# ASD2111.net
KiCad netlist of a schematic drawn in EAGLE
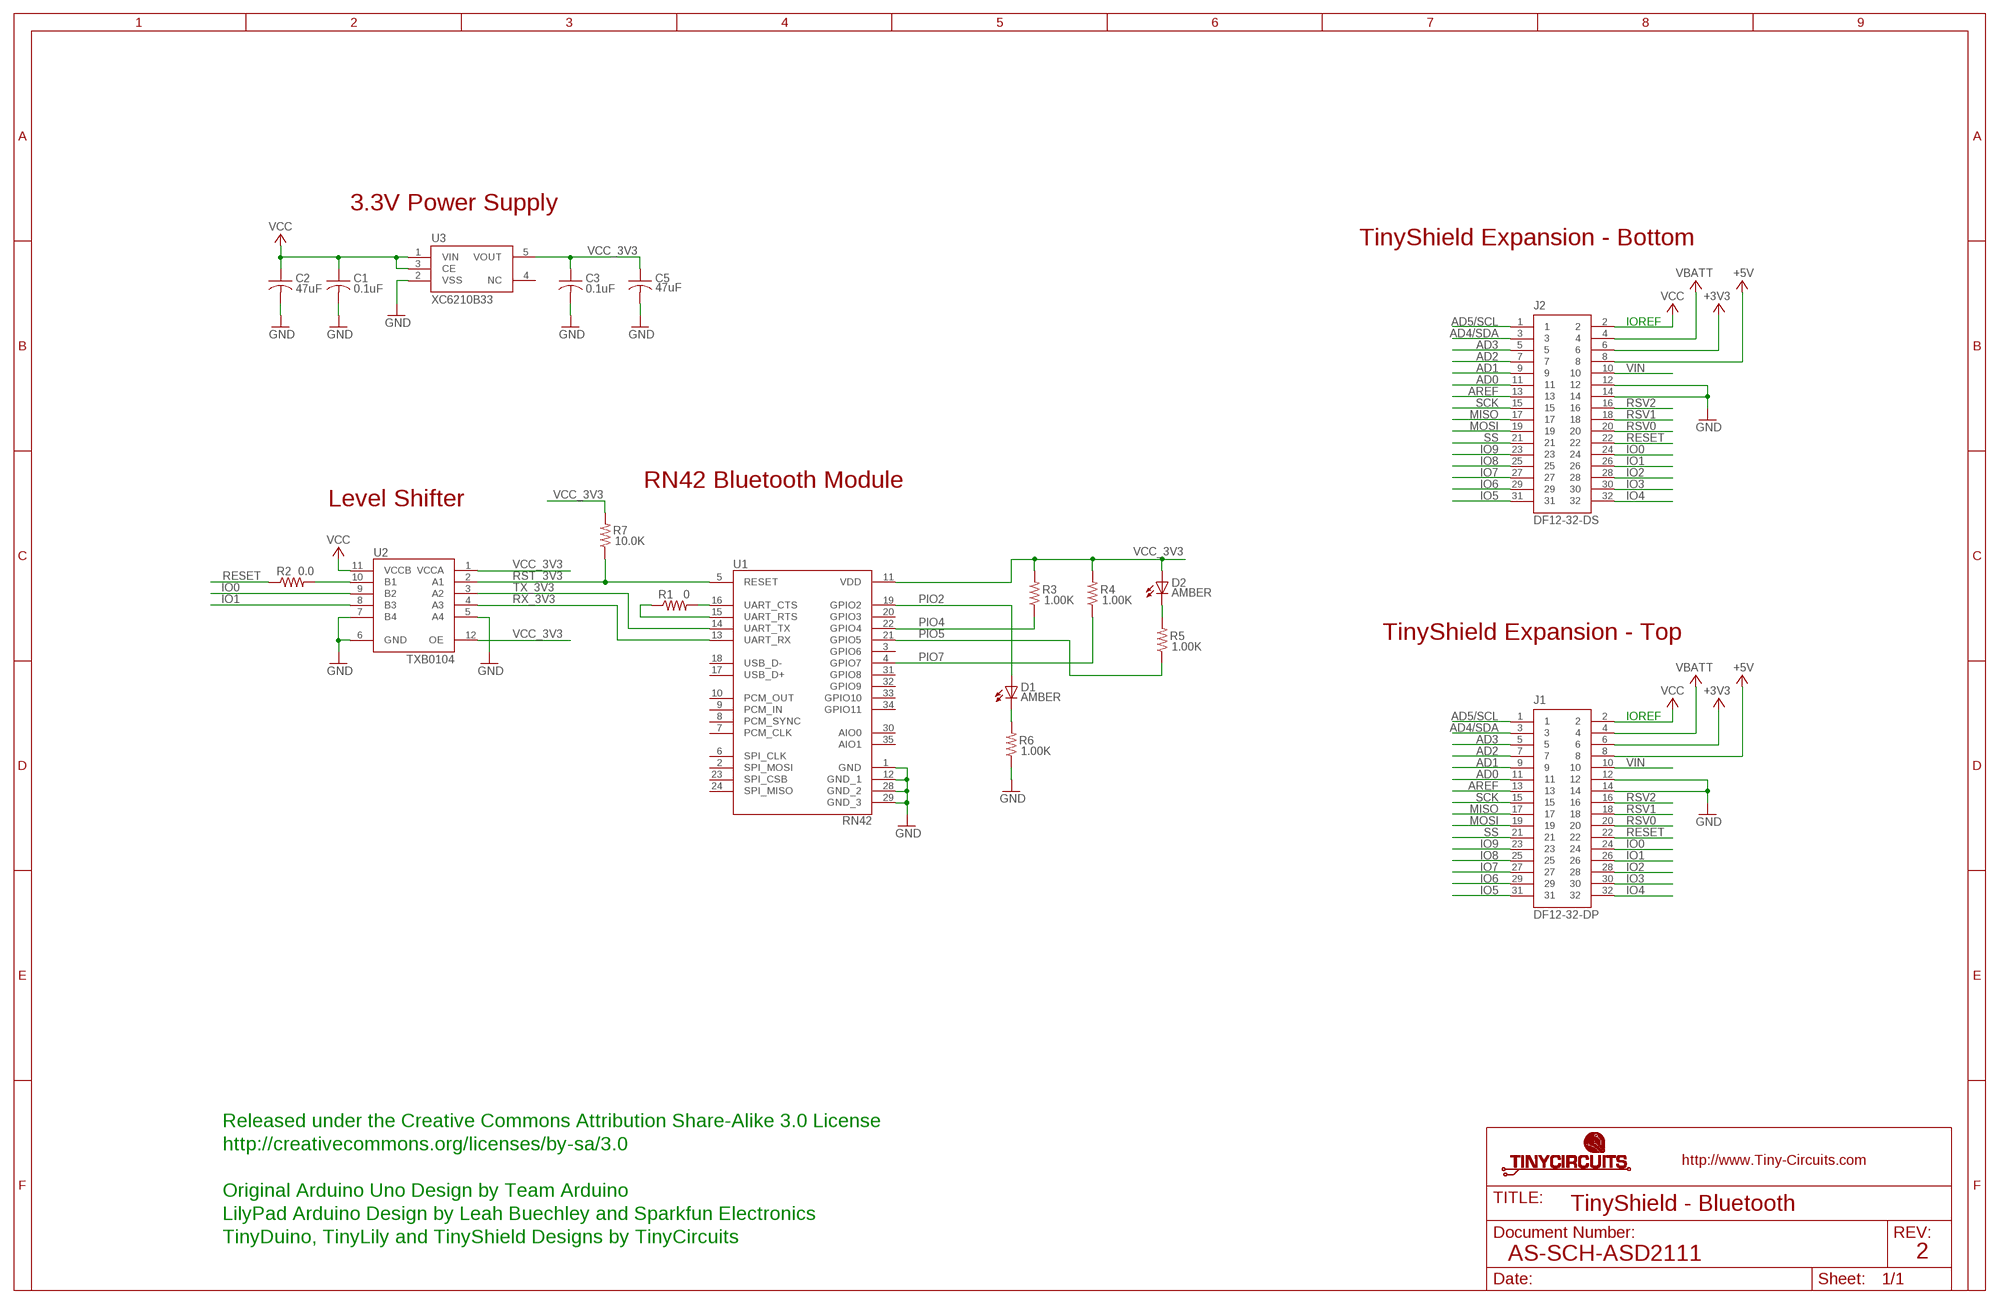
[diagram p0: schematic, sheet 1]

(export (version "E")
  (design (tool "Eeschema 10.0.6"))
  (components
    (comp (ref "C1")
      (value "0.1uF")
      (footprint "eagle-import:C0402")
      (fields (field (name "PARTNO") "AS-ITM-00008") (field (name "PARTNO_1") "AS-ITM-00008"))
      (libsource (lib "eagle-import") (part "AS-ITM-00008"))
    )
    (comp (ref "C2")
      (value "47uF")
      (footprint "eagle-import:C1206")
      (fields (field (name "PARTNUM") "AS-ITM-00049") (field (name "PARTNUM_1") "AS-ITM-00049"))
      (libsource (lib "eagle-import") (part "AS-ITM-00049"))
    )
    (comp (ref "C3")
      (value "0.1uF")
      (footprint "eagle-import:C0402")
      (fields (field (name "PARTNO") "AS-ITM-00008") (field (name "PARTNO_1") "AS-ITM-00008"))
      (libsource (lib "eagle-import") (part "AS-ITM-00008"))
    )
    (comp (ref "C5")
      (value "47uF")
      (footprint "eagle-import:C1206")
      (fields (field (name "PARTNUM") "AS-ITM-00049"))
      (libsource (lib "eagle-import") (part "AS-ITM-00049"))
    )
    (comp (ref "D1")
      (value "AMBER")
      (footprint "eagle-import:LNJ_LED")
      (fields (field (name "PARTNO") "AS-ITM-00026"))
      (libsource (lib "eagle-import") (part "AS-ITM-00026"))
    )
    (comp (ref "D2")
      (value "AMBER")
      (footprint "eagle-import:LNJ_LED")
      (fields (field (name "PARTNO") "AS-ITM-00026") (field (name "PARTNO_1") "AS-ITM-00026"))
      (libsource (lib "eagle-import") (part "AS-ITM-00026"))
    )
    (comp (ref "J1")
      (value "DF12-32-DP")
      (footprint "eagle-import:DF12-32-DP")
      (fields (field (name "PARTNO") "AS-ITM-00015") (field (name "PARTNO_1") "AS-ITM-00015"))
      (libsource (lib "eagle-import") (part "AS-ITM-00015"))
    )
    (comp (ref "J2")
      (value "DF12-32-DS")
      (footprint "eagle-import:DF12-32-DS")
      (fields (field (name "PARTNO") "AS-ITM-00012") (field (name "PARTNO_1") "AS-ITM-00012"))
      (libsource (lib "eagle-import") (part "AS-ITM-00012"))
    )
    (comp (ref "R1")
      (value "0")
      (footprint "eagle-import:0402_SHORT")
      (libsource (lib "eagle-import") (part "AS-ITM-000760402_SHORT"))
    )
    (comp (ref "R2")
      (value "0.0")
      (footprint "eagle-import:0402")
      (fields (field (name "PARTNO") "AS-ITM-00076"))
      (libsource (lib "eagle-import") (part "AS-ITM-00076"))
    )
    (comp (ref "R3")
      (value "1.00K")
      (footprint "eagle-import:0402")
      (fields (field (name "PARTNO") "AS-ITM-00003"))
      (libsource (lib "eagle-import") (part "AS-ITM-00003"))
    )
    (comp (ref "R4")
      (value "1.00K")
      (footprint "eagle-import:0402")
      (fields (field (name "PARTNO") "AS-ITM-00003") (field (name "PARTNO_1") "AS-ITM-00003"))
      (libsource (lib "eagle-import") (part "AS-ITM-00003"))
    )
    (comp (ref "R5")
      (value "1.00K")
      (footprint "eagle-import:0402")
      (fields (field (name "PARTNO") "AS-ITM-00003") (field (name "PARTNO_1") "AS-ITM-00003"))
      (libsource (lib "eagle-import") (part "AS-ITM-00003"))
    )
    (comp (ref "R6")
      (value "1.00K")
      (footprint "eagle-import:0402")
      (fields (field (name "PARTNO") "AS-ITM-00003") (field (name "PARTNO_1") "AS-ITM-00003"))
      (libsource (lib "eagle-import") (part "AS-ITM-00003"))
    )
    (comp (ref "R7")
      (value "10.0K")
      (footprint "eagle-import:0402")
      (fields (field (name "PARTNO") "AS-ITM-00032"))
      (libsource (lib "eagle-import") (part "AS-ITM-00032"))
    )
    (comp (ref "U1")
      (value "RN42")
      (footprint "eagle-import:RN42_BLUETOOTH_MODULE")
      (fields (field (name "PARTNO") "AS-ITM-00071"))
      (libsource (lib "eagle-import") (part "AS-ITM-00071"))
    )
    (comp (ref "U2")
      (value "TXB0104")
      (footprint "eagle-import:UQFN-12")
      (fields (field (name "PARTNO") "AS-ITM-00048"))
      (libsource (lib "eagle-import") (part "AS-ITM-00048"))
    )
    (comp (ref "U3")
      (value "XC6210B33")
      (footprint "eagle-import:SOT-25")
      (fields (field (name "PARTNO") "AS-ITM-00046"))
      (libsource (lib "eagle-import") (part "AS-ITM-00046"))
    )
  )
  (nets
    (net (code "1") (name "+3V3") (class "Default")
      (node (ref "J1") (pin "6") (pinfunction "6_6") (pintype "bidirectional"))
      (node (ref "J2") (pin "6") (pinfunction "6_6") (pintype "bidirectional"))
    )
    (net (code "2") (name "+5V") (class "Default")
      (node (ref "J1") (pin "8") (pinfunction "8_8") (pintype "bidirectional"))
      (node (ref "J2") (pin "8") (pinfunction "8_8") (pintype "bidirectional"))
    )
    (net (code "3") (name "/AD0") (class "Default")
      (node (ref "J1") (pin "11") (pinfunction "11_11") (pintype "bidirectional"))
      (node (ref "J2") (pin "11") (pinfunction "11_11") (pintype "bidirectional"))
    )
    (net (code "4") (name "/AD1") (class "Default")
      (node (ref "J1") (pin "9") (pinfunction "9_9") (pintype "bidirectional"))
      (node (ref "J2") (pin "9") (pinfunction "9_9") (pintype "bidirectional"))
    )
    (net (code "5") (name "/AD2") (class "Default")
      (node (ref "J1") (pin "7") (pinfunction "7_7") (pintype "bidirectional"))
      (node (ref "J2") (pin "7") (pinfunction "7_7") (pintype "bidirectional"))
    )
    (net (code "6") (name "/AD3") (class "Default")
      (node (ref "J1") (pin "5") (pinfunction "5_5") (pintype "bidirectional"))
      (node (ref "J2") (pin "5") (pinfunction "5_5") (pintype "bidirectional"))
    )
    (net (code "7") (name "/AD4{slash}SDA") (class "Default")
      (node (ref "J1") (pin "3") (pinfunction "3_3") (pintype "bidirectional"))
      (node (ref "J2") (pin "3") (pinfunction "3_3") (pintype "bidirectional"))
    )
    (net (code "8") (name "/AD5{slash}SCL") (class "Default")
      (node (ref "J1") (pin "1") (pinfunction "1_1") (pintype "bidirectional"))
      (node (ref "J2") (pin "1") (pinfunction "1_1") (pintype "bidirectional"))
    )
    (net (code "9") (name "/AREF") (class "Default")
      (node (ref "J1") (pin "13") (pinfunction "13_13") (pintype "bidirectional"))
      (node (ref "J2") (pin "13") (pinfunction "13_13") (pintype "bidirectional"))
    )
    (net (code "10") (name "/IO0") (class "Default")
      (node (ref "J1") (pin "24") (pinfunction "24_24") (pintype "bidirectional"))
      (node (ref "J2") (pin "24") (pinfunction "24_24") (pintype "bidirectional"))
      (node (ref "U2") (pin "9") (pinfunction "B2_9") (pintype "bidirectional"))
    )
    (net (code "11") (name "/IO1") (class "Default")
      (node (ref "J1") (pin "26") (pinfunction "26_26") (pintype "bidirectional"))
      (node (ref "J2") (pin "26") (pinfunction "26_26") (pintype "bidirectional"))
      (node (ref "U2") (pin "8") (pinfunction "B3_8") (pintype "bidirectional"))
    )
    (net (code "12") (name "/IO2") (class "Default")
      (node (ref "J1") (pin "28") (pinfunction "28_28") (pintype "bidirectional"))
      (node (ref "J2") (pin "28") (pinfunction "28_28") (pintype "bidirectional"))
    )
    (net (code "13") (name "/IO3") (class "Default")
      (node (ref "J1") (pin "30") (pinfunction "30_30") (pintype "bidirectional"))
      (node (ref "J2") (pin "30") (pinfunction "30_30") (pintype "bidirectional"))
    )
    (net (code "14") (name "/IO4") (class "Default")
      (node (ref "J1") (pin "32") (pinfunction "32_32") (pintype "bidirectional"))
      (node (ref "J2") (pin "32") (pinfunction "32_32") (pintype "bidirectional"))
    )
    (net (code "15") (name "/IO5") (class "Default")
      (node (ref "J1") (pin "31") (pinfunction "31_31") (pintype "bidirectional"))
      (node (ref "J2") (pin "31") (pinfunction "31_31") (pintype "bidirectional"))
    )
    (net (code "16") (name "/IO6") (class "Default")
      (node (ref "J1") (pin "29") (pinfunction "29_29") (pintype "bidirectional"))
      (node (ref "J2") (pin "29") (pinfunction "29_29") (pintype "bidirectional"))
    )
    (net (code "17") (name "/IO7") (class "Default")
      (node (ref "J1") (pin "27") (pinfunction "27_27") (pintype "bidirectional"))
      (node (ref "J2") (pin "27") (pinfunction "27_27") (pintype "bidirectional"))
    )
    (net (code "18") (name "/IO8") (class "Default")
      (node (ref "J1") (pin "25") (pinfunction "25_25") (pintype "bidirectional"))
      (node (ref "J2") (pin "25") (pinfunction "25_25") (pintype "bidirectional"))
    )
    (net (code "19") (name "/IO9") (class "Default")
      (node (ref "J1") (pin "23") (pinfunction "23_23") (pintype "bidirectional"))
      (node (ref "J2") (pin "23") (pinfunction "23_23") (pintype "bidirectional"))
    )
    (net (code "20") (name "/MISO") (class "Default")
      (node (ref "J1") (pin "17") (pinfunction "17_17") (pintype "bidirectional"))
      (node (ref "J2") (pin "17") (pinfunction "17_17") (pintype "bidirectional"))
    )
    (net (code "21") (name "/MOSI") (class "Default")
      (node (ref "J1") (pin "19") (pinfunction "19_19") (pintype "bidirectional"))
      (node (ref "J2") (pin "19") (pinfunction "19_19") (pintype "bidirectional"))
    )
    (net (code "22") (name "/PIO2") (class "Default")
      (node (ref "D1") (pin "A") (pinfunction "A_A") (pintype "passive"))
      (node (ref "U1") (pin "19") (pinfunction "GPIO2_19") (pintype "bidirectional"))
    )
    (net (code "23") (name "/PIO4") (class "Default")
      (node (ref "R3") (pin "1") (pinfunction "1_1") (pintype "passive"))
      (node (ref "U1") (pin "22") (pinfunction "GPIO4_22") (pintype "bidirectional"))
    )
    (net (code "24") (name "/PIO5") (class "Default")
      (node (ref "R5") (pin "1") (pinfunction "1_1") (pintype "passive"))
      (node (ref "U1") (pin "21") (pinfunction "GPIO5_21") (pintype "bidirectional"))
    )
    (net (code "25") (name "/PIO7") (class "Default")
      (node (ref "R4") (pin "1") (pinfunction "1_1") (pintype "passive"))
      (node (ref "U1") (pin "4") (pinfunction "GPIO7_4") (pintype "bidirectional"))
    )
    (net (code "26") (name "/RESET") (class "Default")
      (node (ref "J1") (pin "22") (pinfunction "22_22") (pintype "bidirectional"))
      (node (ref "J2") (pin "22") (pinfunction "22_22") (pintype "bidirectional"))
      (node (ref "R2") (pin "1") (pinfunction "1_1") (pintype "passive"))
    )
    (net (code "27") (name "/RST_3V3") (class "Default")
      (node (ref "R7") (pin "1") (pinfunction "1_1") (pintype "passive"))
      (node (ref "U1") (pin "5") (pinfunction "RESET_5") (pintype "bidirectional"))
      (node (ref "U2") (pin "2") (pinfunction "A1_2") (pintype "bidirectional"))
    )
    (net (code "28") (name "/RSV0") (class "Default")
      (node (ref "J1") (pin "20") (pinfunction "20_20") (pintype "bidirectional"))
      (node (ref "J2") (pin "20") (pinfunction "20_20") (pintype "bidirectional"))
    )
    (net (code "29") (name "/RSV1") (class "Default")
      (node (ref "J1") (pin "18") (pinfunction "18_18") (pintype "bidirectional"))
      (node (ref "J2") (pin "18") (pinfunction "18_18") (pintype "bidirectional"))
    )
    (net (code "30") (name "/RSV2") (class "Default")
      (node (ref "J1") (pin "16") (pinfunction "16_16") (pintype "bidirectional"))
      (node (ref "J2") (pin "16") (pinfunction "16_16") (pintype "bidirectional"))
    )
    (net (code "31") (name "/RX_3V3") (class "Default")
      (node (ref "U1") (pin "13") (pinfunction "UART_RX_13") (pintype "bidirectional"))
      (node (ref "U2") (pin "4") (pinfunction "A3_4") (pintype "bidirectional"))
    )
    (net (code "32") (name "/SCK") (class "Default")
      (node (ref "J1") (pin "15") (pinfunction "15_15") (pintype "bidirectional"))
      (node (ref "J2") (pin "15") (pinfunction "15_15") (pintype "bidirectional"))
    )
    (net (code "33") (name "/SS") (class "Default")
      (node (ref "J1") (pin "21") (pinfunction "21_21") (pintype "bidirectional"))
      (node (ref "J2") (pin "21") (pinfunction "21_21") (pintype "bidirectional"))
    )
    (net (code "34") (name "/TX_3V3") (class "Default")
      (node (ref "U1") (pin "14") (pinfunction "UART_TX_14") (pintype "bidirectional"))
      (node (ref "U2") (pin "3") (pinfunction "A2_3") (pintype "bidirectional"))
    )
    (net (code "35") (name "/VCC_3V3") (class "Default")
      (node (ref "C3") (pin "1") (pinfunction "1_1") (pintype "passive"))
      (node (ref "C5") (pin "1") (pinfunction "1_1") (pintype "passive"))
      (node (ref "D2") (pin "A") (pinfunction "A_A") (pintype "passive"))
      (node (ref "R3") (pin "2") (pinfunction "2_2") (pintype "passive"))
      (node (ref "R4") (pin "2") (pinfunction "2_2") (pintype "passive"))
      (node (ref "R7") (pin "2") (pinfunction "2_2") (pintype "passive"))
      (node (ref "U1") (pin "11") (pinfunction "VDD_11") (pintype "bidirectional"))
      (node (ref "U2") (pin "1") (pinfunction "VCCA_1") (pintype "bidirectional"))
      (node (ref "U2") (pin "12") (pinfunction "OE_12") (pintype "bidirectional"))
      (node (ref "U3") (pin "5") (pinfunction "VOUT_5") (pintype "bidirectional"))
    )
    (net (code "36") (name "/VIN") (class "Default")
      (node (ref "J1") (pin "10") (pinfunction "10_10") (pintype "bidirectional"))
      (node (ref "J2") (pin "10") (pinfunction "10_10") (pintype "bidirectional"))
    )
    (net (code "37") (name "GND") (class "Default")
      (node (ref "C1") (pin "2") (pinfunction "2_2") (pintype "passive"))
      (node (ref "C2") (pin "2") (pinfunction "2_2") (pintype "passive"))
      (node (ref "C3") (pin "2") (pinfunction "2_2") (pintype "passive"))
      (node (ref "C5") (pin "2") (pinfunction "2_2") (pintype "passive"))
      (node (ref "J1") (pin "12") (pinfunction "12_12") (pintype "bidirectional"))
      (node (ref "J1") (pin "14") (pinfunction "14_14") (pintype "bidirectional"))
      (node (ref "J2") (pin "12") (pinfunction "12_12") (pintype "bidirectional"))
      (node (ref "J2") (pin "14") (pinfunction "14_14") (pintype "bidirectional"))
      (node (ref "R6") (pin "1") (pinfunction "1_1") (pintype "passive"))
      (node (ref "U1") (pin "1") (pinfunction "GND_1") (pintype "bidirectional"))
      (node (ref "U1") (pin "12") (pinfunction "GND_1_12") (pintype "bidirectional"))
      (node (ref "U1") (pin "28") (pinfunction "GND_2_28") (pintype "bidirectional"))
      (node (ref "U1") (pin "29") (pinfunction "GND_3_29") (pintype "bidirectional"))
      (node (ref "U2") (pin "5") (pinfunction "A4_5") (pintype "bidirectional"))
      (node (ref "U2") (pin "6") (pinfunction "GND_6") (pintype "bidirectional"))
      (node (ref "U2") (pin "7") (pinfunction "B4_7") (pintype "bidirectional"))
      (node (ref "U3") (pin "2") (pinfunction "VSS_2") (pintype "power_in"))
    )
    (net (code "38") (name "Net-(D1-PadC)") (class "Default")
      (node (ref "D1") (pin "C") (pinfunction "C_C") (pintype "passive"))
      (node (ref "R6") (pin "2") (pinfunction "2_2") (pintype "passive"))
    )
    (net (code "39") (name "Net-(D2-PadC)") (class "Default")
      (node (ref "D2") (pin "C") (pinfunction "C_C") (pintype "passive"))
      (node (ref "R5") (pin "2") (pinfunction "2_2") (pintype "passive"))
    )
    (net (code "40") (name "Net-(U1-UART_CTS)") (class "Default")
      (node (ref "R1") (pin "2") (pinfunction "2_2") (pintype "passive"))
      (node (ref "U1") (pin "16") (pinfunction "UART_CTS_16") (pintype "bidirectional"))
    )
    (net (code "41") (name "Net-(U1-UART_RTS)") (class "Default")
      (node (ref "R1") (pin "1") (pinfunction "1_1") (pintype "passive"))
      (node (ref "U1") (pin "15") (pinfunction "UART_RTS_15") (pintype "bidirectional"))
    )
    (net (code "42") (name "Net-(U2-B1)") (class "Default")
      (node (ref "R2") (pin "2") (pinfunction "2_2") (pintype "passive"))
      (node (ref "U2") (pin "10") (pinfunction "B1_10") (pintype "bidirectional"))
    )
    (net (code "43") (name "VBATT") (class "Default")
      (node (ref "J1") (pin "4") (pinfunction "4_4") (pintype "bidirectional"))
      (node (ref "J2") (pin "4") (pinfunction "4_4") (pintype "bidirectional"))
    )
    (net (code "44") (name "VCC") (class "Default")
      (node (ref "C1") (pin "1") (pinfunction "1_1") (pintype "passive"))
      (node (ref "C2") (pin "1") (pinfunction "1_1") (pintype "passive"))
      (node (ref "J1") (pin "2") (pinfunction "2_2") (pintype "bidirectional"))
      (node (ref "J2") (pin "2") (pinfunction "2_2") (pintype "bidirectional"))
      (node (ref "U2") (pin "11") (pinfunction "VCCB_11") (pintype "bidirectional"))
      (node (ref "U3") (pin "1") (pinfunction "VIN_1") (pintype "bidirectional"))
      (node (ref "U3") (pin "3") (pinfunction "CE_3") (pintype "bidirectional"))
    )
    (net (code "45") (name "unconnected-(U1-AIO0-Pad30)") (class "Default")
      (node (ref "U1") (pin "30") (pinfunction "AIO0_30") (pintype "bidirectional"))
    )
    (net (code "46") (name "unconnected-(U1-AIO1-Pad35)") (class "Default")
      (node (ref "U1") (pin "35") (pinfunction "AIO1_35") (pintype "bidirectional"))
    )
    (net (code "47") (name "unconnected-(U1-GPIO3-Pad20)") (class "Default")
      (node (ref "U1") (pin "20") (pinfunction "GPIO3_20") (pintype "bidirectional"))
    )
    (net (code "48") (name "unconnected-(U1-GPIO6-Pad3)") (class "Default")
      (node (ref "U1") (pin "3") (pinfunction "GPIO6_3") (pintype "bidirectional"))
    )
    (net (code "49") (name "unconnected-(U1-GPIO8-Pad31)") (class "Default")
      (node (ref "U1") (pin "31") (pinfunction "GPIO8_31") (pintype "bidirectional"))
    )
    (net (code "50") (name "unconnected-(U1-GPIO9-Pad32)") (class "Default")
      (node (ref "U1") (pin "32") (pinfunction "GPIO9_32") (pintype "bidirectional"))
    )
    (net (code "51") (name "unconnected-(U1-GPIO10-Pad33)") (class "Default")
      (node (ref "U1") (pin "33") (pinfunction "GPIO10_33") (pintype "bidirectional"))
    )
    (net (code "52") (name "unconnected-(U1-GPIO11-Pad34)") (class "Default")
      (node (ref "U1") (pin "34") (pinfunction "GPIO11_34") (pintype "bidirectional"))
    )
    (net (code "53") (name "unconnected-(U1-PCM_CLK-Pad7)") (class "Default")
      (node (ref "U1") (pin "7") (pinfunction "PCM_CLK_7") (pintype "bidirectional"))
    )
    (net (code "54") (name "unconnected-(U1-PCM_IN-Pad9)") (class "Default")
      (node (ref "U1") (pin "9") (pinfunction "PCM_IN_9") (pintype "bidirectional"))
    )
    (net (code "55") (name "unconnected-(U1-PCM_OUT-Pad10)") (class "Default")
      (node (ref "U1") (pin "10") (pinfunction "PCM_OUT_10") (pintype "bidirectional"))
    )
    (net (code "56") (name "unconnected-(U1-PCM_SYNC-Pad8)") (class "Default")
      (node (ref "U1") (pin "8") (pinfunction "PCM_SYNC_8") (pintype "bidirectional"))
    )
    (net (code "57") (name "unconnected-(U1-SPI_CLK-Pad6)") (class "Default")
      (node (ref "U1") (pin "6") (pinfunction "SPI_CLK_6") (pintype "bidirectional"))
    )
    (net (code "58") (name "unconnected-(U1-SPI_CSB-Pad23)") (class "Default")
      (node (ref "U1") (pin "23") (pinfunction "SPI_CSB_23") (pintype "bidirectional"))
    )
    (net (code "59") (name "unconnected-(U1-SPI_MISO-Pad24)") (class "Default")
      (node (ref "U1") (pin "24") (pinfunction "SPI_MISO_24") (pintype "bidirectional"))
    )
    (net (code "60") (name "unconnected-(U1-SPI_MOSI-Pad2)") (class "Default")
      (node (ref "U1") (pin "2") (pinfunction "SPI_MOSI_2") (pintype "bidirectional"))
    )
    (net (code "61") (name "unconnected-(U1-USB_D+-Pad17)") (class "Default")
      (node (ref "U1") (pin "17") (pinfunction "USB_D+_17") (pintype "bidirectional"))
    )
    (net (code "62") (name "unconnected-(U1-USB_D--Pad18)") (class "Default")
      (node (ref "U1") (pin "18") (pinfunction "USB_D-_18") (pintype "bidirectional"))
    )
    (net (code "63") (name "unconnected-(U3-NC-Pad4)") (class "Default")
      (node (ref "U3") (pin "4") (pinfunction "NC_4") (pintype "bidirectional"))
    )
  )
)
